# ics43432_pi.net
KiCad netlist of a schematic drawn in EAGLE
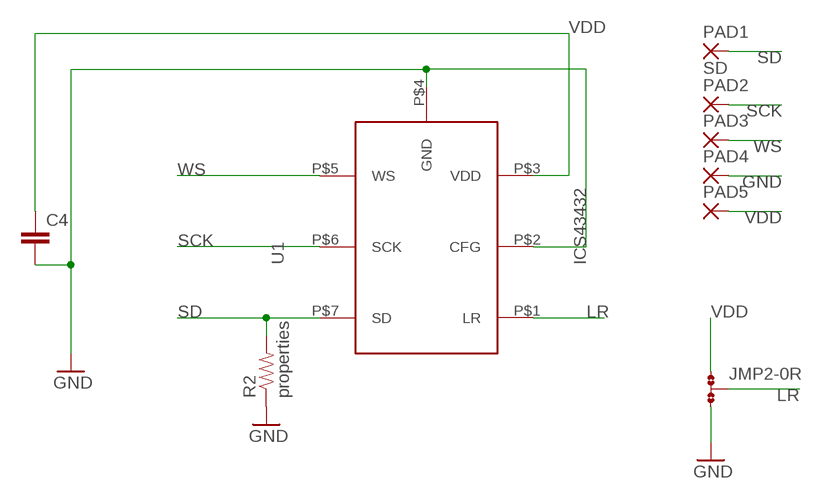
[diagram p0: schematic, sheet 1]

(export (version "E")
  (design (tool "Eeschema 10.0.6"))
  (components
    (comp (ref "C4")
      (value "CAP0402-CAP")
      (footprint "eagle-import:0402-CAP")
      (libsource (lib "eagle-import") (part "CAP0402-CAP"))
    )
    (comp (ref "JMP2")
      (value "0R-JUMPC")
      (footprint "eagle-import:C0R-JMP")
      (libsource (lib "eagle-import") (part "0R-JUMPC"))
    )
    (comp (ref "PAD1")
      (value "SD")
      (footprint "eagle-import:SMD1,27-2,54")
      (libsource (lib "eagle-import") (part "SMD2"))
    )
    (comp (ref "PAD2")
      (value "SMD2")
      (footprint "eagle-import:SMD1,27-2,54")
      (libsource (lib "eagle-import") (part "SMD2"))
    )
    (comp (ref "PAD3")
      (value "SMD2")
      (footprint "eagle-import:SMD1,27-2,54")
      (libsource (lib "eagle-import") (part "SMD2"))
    )
    (comp (ref "PAD4")
      (value "SMD2")
      (footprint "eagle-import:SMD1,27-2,54")
      (libsource (lib "eagle-import") (part "SMD2"))
    )
    (comp (ref "PAD5")
      (value "SMD2")
      (footprint "eagle-import:SMD1,27-2,54")
      (libsource (lib "eagle-import") (part "SMD2"))
    )
    (comp (ref "R2")
      (value "properties")
      (footprint "eagle-import:0402-RES")
      (libsource (lib "eagle-import") (part "RESISTOR0402-RES"))
    )
    (comp (ref "U1")
      (value "ICS43432")
      (footprint "eagle-import:ICS43432")
      (libsource (lib "eagle-import") (part "ICS43432"))
    )
  )
  (nets
    (net (code "1") (name "/LR") (class "Default")
      (node (ref "JMP2") (pin "2") (pinfunction "2_2") (pintype "passive"))
      (node (ref "U1") (pin "P$1") (pinfunction "LR_P$1") (pintype "bidirectional"))
    )
    (net (code "2") (name "/SCK") (class "Default")
      (node (ref "PAD2") (pin "1") (pinfunction "P_1") (pintype "passive"))
      (node (ref "U1") (pin "P$6") (pinfunction "SCK_P$6") (pintype "bidirectional"))
    )
    (net (code "3") (name "/SD") (class "Default")
      (node (ref "PAD1") (pin "1") (pinfunction "P_1") (pintype "passive"))
      (node (ref "R2") (pin "2") (pinfunction "2_2") (pintype "passive"))
      (node (ref "U1") (pin "P$7") (pinfunction "SD_P$7") (pintype "bidirectional"))
    )
    (net (code "4") (name "/VDD") (class "Default")
      (node (ref "C4") (pin "1") (pinfunction "1_1") (pintype "passive"))
      (node (ref "JMP2") (pin "1") (pinfunction "1_1") (pintype "passive"))
      (node (ref "PAD5") (pin "1") (pinfunction "P_1") (pintype "passive"))
      (node (ref "U1") (pin "P$3") (pinfunction "VDD_P$3") (pintype "bidirectional"))
    )
    (net (code "5") (name "/WS") (class "Default")
      (node (ref "PAD3") (pin "1") (pinfunction "P_1") (pintype "passive"))
      (node (ref "U1") (pin "P$5") (pinfunction "WS_P$5") (pintype "bidirectional"))
    )
    (net (code "6") (name "GND") (class "Default")
      (node (ref "C4") (pin "2") (pinfunction "2_2") (pintype "passive"))
      (node (ref "JMP2") (pin "3") (pinfunction "3_3") (pintype "passive"))
      (node (ref "PAD4") (pin "1") (pinfunction "P_1") (pintype "passive"))
      (node (ref "R2") (pin "1") (pinfunction "1_1") (pintype "passive"))
      (node (ref "U1") (pin "P$2") (pinfunction "CFG_P$2") (pintype "bidirectional"))
      (node (ref "U1") (pin "P$4") (pinfunction "GND_P$4") (pintype "bidirectional"))
    )
  )
)
